# Exterior.net
KiCad netlist of a schematic drawn in EAGLE
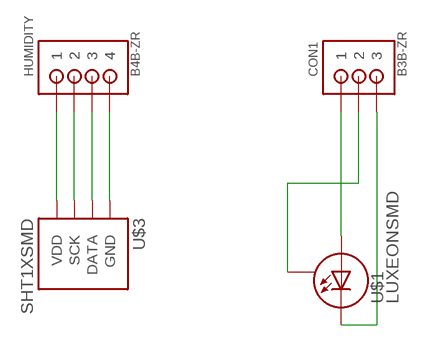
[diagram p0: schematic, sheet 1]

(export (version "E")
  (design (tool "Eeschema 10.0.6"))
  (components
    (comp (ref "CON1")
      (value "B3B-ZR")
      (footprint "eagle-import:B3B-ZR")
      (libsource (lib "eagle-import") (part "B3B-ZR"))
    )
    (comp (ref "HUMIDITY")
      (value "B4B-ZR")
      (footprint "eagle-import:B4B-ZR")
      (libsource (lib "eagle-import") (part "B4B-ZR"))
    )
    (comp (ref "U$1")
      (value "LUXEONSMD")
      (footprint "eagle-import:LUXEON")
      (libsource (lib "eagle-import") (part "LUXEONSMD"))
    )
    (comp (ref "U$3")
      (value "SHT1XSMD")
      (footprint "eagle-import:SHT1X")
      (libsource (lib "eagle-import") (part "SHT1XSMD"))
    )
  )
  (nets
    (net (code "1") (name "Net-(CON1-Pad1)") (class "Default")
      (node (ref "CON1") (pin "1") (pinfunction "1_1") (pintype "bidirectional"))
      (node (ref "U$1") (pin "A") (pinfunction "A_A") (pintype "passive"))
    )
    (net (code "2") (name "Net-(CON1-Pad2)") (class "Default")
      (node (ref "CON1") (pin "2") (pinfunction "2_2") (pintype "bidirectional"))
      (node (ref "U$1") (pin "S") (pinfunction "S_S") (pintype "bidirectional"))
    )
    (net (code "3") (name "Net-(CON1-Pad3)") (class "Default")
      (node (ref "CON1") (pin "3") (pinfunction "3_3") (pintype "bidirectional"))
      (node (ref "U$1") (pin "C") (pinfunction "C_C") (pintype "passive"))
    )
    (net (code "4") (name "Net-(U$3-DATA)") (class "Default")
      (node (ref "HUMIDITY") (pin "3") (pinfunction "3_3") (pintype "bidirectional"))
      (node (ref "U$3") (pin "2") (pinfunction "DATA_2") (pintype "bidirectional"))
    )
    (net (code "5") (name "Net-(U$3-GND)") (class "Default")
      (node (ref "HUMIDITY") (pin "4") (pinfunction "4_4") (pintype "bidirectional"))
      (node (ref "U$3") (pin "1") (pinfunction "GND_1") (pintype "power_in"))
    )
    (net (code "6") (name "Net-(U$3-SCK)") (class "Default")
      (node (ref "HUMIDITY") (pin "2") (pinfunction "2_2") (pintype "bidirectional"))
      (node (ref "U$3") (pin "3") (pinfunction "SCK_3") (pintype "input"))
    )
    (net (code "7") (name "Net-(U$3-VDD)") (class "Default")
      (node (ref "HUMIDITY") (pin "1") (pinfunction "1_1") (pintype "bidirectional"))
      (node (ref "U$3") (pin "4") (pinfunction "VDD_4") (pintype "power_in"))
    )
  )
)
